# 4_mcu.net
KiCad netlist of a schematic drawn in Altium Designer
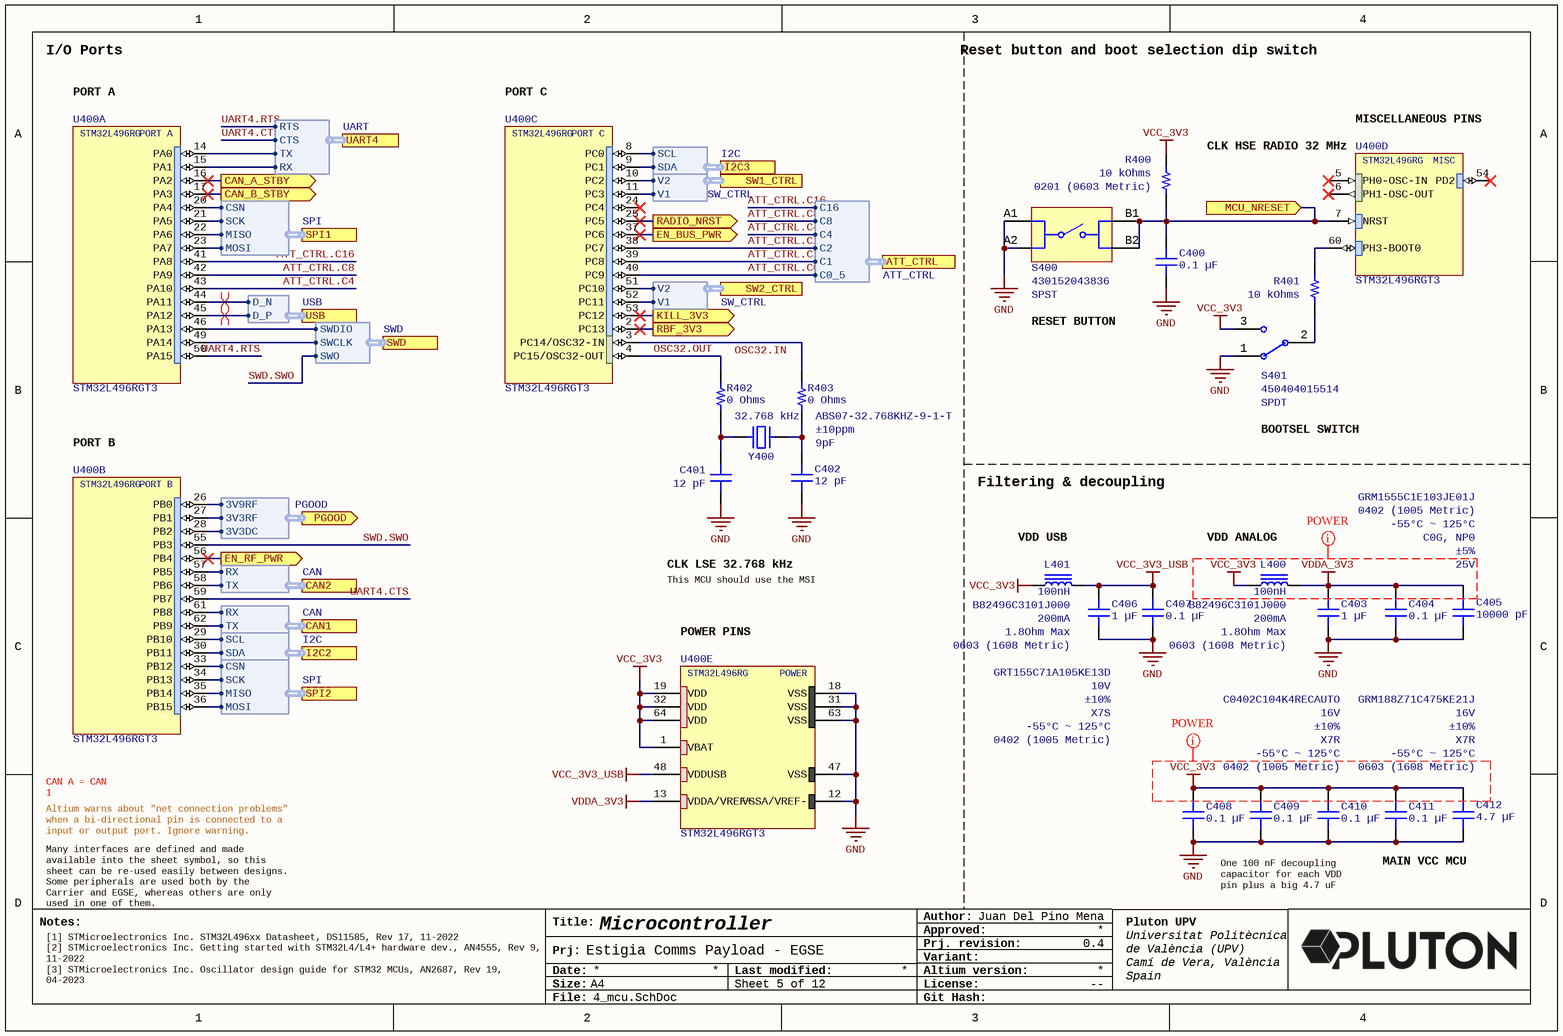
[diagram p0: 4_mcu.SchDoc]

(export (version "E")
  (design (tool "Eeschema 10.0.6"))
  (components
    (comp (ref "C400")
      (value "0.1 µF")
      (footprint "CAP 0402_1005")
      (description "CAP CER 0402 0.1UF 16V X7R 10%")
      (fields (field (name "PART NUMBER") "C0402C104K4RECAUTO") (field (name "MANUFACTURER") "KEMET"))
      (libsource (lib "Celestial Altium Library - altium_library") (part "Capacitor"))
    )
    (comp (ref "C401")
      (value "12 pF")
      (footprint "CAP 0201_0603")
      (description "CAP CER 12PF 25V C0G/NP0 0201")
      (fields (field (name "PART NUMBER") "CBR02C120F3GAC") (field (name "MANUFACTURER") "KEMET"))
      (libsource (lib "Celestial Altium Library - altium_library") (part "Capacitor"))
    )
    (comp (ref "C402")
      (value "12 pF")
      (footprint "CAP 0201_0603")
      (description "CAP CER 12PF 25V C0G/NP0 0201")
      (fields (field (name "PART NUMBER") "CBR02C120F3GAC") (field (name "MANUFACTURER") "KEMET"))
      (libsource (lib "Celestial Altium Library - altium_library") (part "Capacitor"))
    )
    (comp (ref "C403")
      (value "1 µF")
      (footprint "CAP 0402_1005")
      (description "CAP CER 1UF 10V X7S 0402")
      (fields
        (field (name "PART NUMBER") "GRT155C71A105KE13D")
        (field (name "MANUFACTURER") "Murata Electronics")
      )
      (libsource (lib "Celestial Altium Library - altium_library") (part "Capacitor"))
    )
    (comp (ref "C404")
      (value "0.1 µF")
      (footprint "CAP 0402_1005")
      (description "CAP CER 0402 0.1UF 16V X7R 10%")
      (fields (field (name "PART NUMBER") "C0402C104K4RECAUTO") (field (name "MANUFACTURER") "KEMET"))
      (libsource (lib "Celestial Altium Library - altium_library") (part "Capacitor"))
    )
    (comp (ref "C405")
      (value "10000 pF")
      (footprint "CAP 0402_1005")
      (description "CAP CER 10000PF 25V C0G/NP0 0402")
      (fields
        (field (name "PART NUMBER") "GRM1555C1E103JE01J")
        (field (name "DEVICE PACKAGE") "0402 (1005 Metric)")
        (field (name "MANUFACTURER") "Murata Electronics")
        (field (name "OPERATING TEMPERATURE") "-55°C ~ 125°C")
        (field (name "TEMPERATURE COEFFICIENT") "C0G, NP0")
        (field (name "TOLERANCE") "±5%")
        (field (name "VOLTAGE - RATED") "25V")
      )
      (libsource (lib "Celestial Altium Library - altium_library") (part "Capacitor"))
    )
    (comp (ref "C406")
      (value "1 µF")
      (footprint "CAP 0402_1005")
      (description "CAP CER 1UF 10V X7S 0402")
      (fields
        (field (name "PART NUMBER") "GRT155C71A105KE13D")
        (field (name "DEVICE PACKAGE") "0402 (1005 Metric)")
        (field (name "MANUFACTURER") "Murata Electronics")
        (field (name "OPERATING TEMPERATURE") "-55°C ~ 125°C")
        (field (name "TEMPERATURE COEFFICIENT") "X7S")
        (field (name "TOLERANCE") "±10%")
        (field (name "VOLTAGE - RATED") "10V")
      )
      (libsource (lib "Celestial Altium Library - altium_library") (part "Capacitor"))
    )
    (comp (ref "C407")
      (value "0.1 µF")
      (footprint "CAP 0402_1005")
      (description "CAP CER 0402 0.1UF 16V X7R 10%")
      (fields (field (name "PART NUMBER") "C0402C104K4RECAUTO") (field (name "MANUFACTURER") "KEMET"))
      (libsource (lib "Celestial Altium Library - altium_library") (part "Capacitor"))
    )
    (comp (ref "C408")
      (value "0.1 µF")
      (footprint "CAP 0402_1005")
      (description "CAP CER 0402 0.1UF 16V X7R 10%")
      (fields (field (name "PART NUMBER") "C0402C104K4RECAUTO") (field (name "MANUFACTURER") "KEMET"))
      (libsource (lib "Celestial Altium Library - altium_library") (part "Capacitor"))
    )
    (comp (ref "C409")
      (value "0.1 µF")
      (footprint "CAP 0402_1005")
      (description "CAP CER 0402 0.1UF 16V X7R 10%")
      (fields
        (field (name "PART NUMBER") "C0402C104K4RECAUTO")
        (field (name "MANUFACTURER") "KEMET")
        (field (name "OPERATING TEMPERATURE") "-55°C ~ 125°C")
        (field (name "PACKAGE / CASE") "0402 (1005 Metric)")
        (field (name "TEMPERATURE COEFFICIENT") "X7R")
        (field (name "TOLERANCE") "±10%")
        (field (name "VOLTAGE - RATED") "16V")
      )
      (libsource (lib "Celestial Altium Library - altium_library") (part "Capacitor"))
    )
    (comp (ref "C410")
      (value "0.1 µF")
      (footprint "CAP 0402_1005")
      (description "CAP CER 0402 0.1UF 16V X7R 10%")
      (fields (field (name "PART NUMBER") "C0402C104K4RECAUTO") (field (name "MANUFACTURER") "KEMET"))
      (libsource (lib "Celestial Altium Library - altium_library") (part "Capacitor"))
    )
    (comp (ref "C411")
      (value "0.1 µF")
      (footprint "CAP 0402_1005")
      (description "CAP CER 0402 0.1UF 16V X7R 10%")
      (fields (field (name "PART NUMBER") "C0402C104K4RECAUTO") (field (name "MANUFACTURER") "KEMET"))
      (libsource (lib "Celestial Altium Library - altium_library") (part "Capacitor"))
    )
    (comp (ref "C412")
      (value "4.7 µF")
      (footprint "CAP 0603_1608")
      (description "CAP CER 4.7UF 16V X7R 0603")
      (fields
        (field (name "PART NUMBER") "GRM188Z71C475KE21J")
        (field (name "DEVICE PACKAGE") "0603 (1608 Metric)")
        (field (name "MANUFACTURER") "Murata Electronics")
        (field (name "OPERATING TEMPERATURE") "-55°C ~ 125°C")
        (field (name "TEMPERATURE COEFFICIENT") "X7R")
        (field (name "TOLERANCE") "±10%")
        (field (name "VOLTAGE - RATED") "16V")
      )
      (libsource (lib "Celestial Altium Library - altium_library") (part "Capacitor"))
    )
    (comp (ref "L400")
      (value "100nH")
      (footprint "IND 0603_1608 RF WW")
      (description "FIXED IND 100NH 200MA 1.8 OHM")
      (fields
        (field (name "PART NUMBER") "B82496C3101J000")
        (field (name "CURRENT RATING (AMPS)") "200mA")
        (field (name "DC RESISTANCE (DCR)") "1.8Ohm Max")
        (field (name "DEVICE PACKAGE") "0603 (1608 Metric)")
        (field (name "MANUFACTURER") "TDK Electronics Inc.")
        (field (name "TOLERANCE") "±5%")
      )
      (libsource (lib "Celestial Altium Library - altium_library") (part "Inductor"))
    )
    (comp (ref "L401")
      (value "100nH")
      (footprint "IND 0603_1608 RF WW")
      (description "FIXED IND 100NH 200MA 1.8 OHM")
      (fields
        (field (name "PART NUMBER") "B82496C3101J000")
        (field (name "CURRENT RATING (AMPS)") "200mA")
        (field (name "DC RESISTANCE (DCR)") "1.8Ohm Max")
        (field (name "DEVICE PACKAGE") "0603 (1608 Metric)")
        (field (name "MANUFACTURER") "TDK Electronics Inc.")
        (field (name "TOLERANCE") "±5%")
      )
      (libsource (lib "Celestial Altium Library - altium_library") (part "Inductor"))
    )
    (comp (ref "R400")
      (value "10 kOhms")
      (footprint "RES 0201_0603")
      (description "RES SMD 10K OHM 1% 1/20W 0201")
      (fields
        (field (name "PART NUMBER") "AF0201FR-0710KL")
        (field (name "MANUFACTURER") "Yageo")
        (field (name "PACKAGE / CASE") "0201 (0603 Metric)")
      )
      (libsource (lib "Celestial Altium Library - altium_library") (part "Resistor"))
    )
    (comp (ref "R401")
      (value "10 kOhms")
      (footprint "RES 0201_0603")
      (description "RES SMD 10K OHM 1% 1/20W 0201")
      (fields (field (name "PART NUMBER") "AF0201FR-0710KL") (field (name "MANUFACTURER") "Yageo"))
      (libsource (lib "Celestial Altium Library - altium_library") (part "Resistor"))
    )
    (comp (ref "R402")
      (value "0 Ohms")
      (footprint "RES 0201_0603")
      (description "RES SMD 0 OHM JUMPER 1/20W 0201")
      (fields (field (name "PART NUMBER") "AC0201JR-070RL") (field (name "MANUFACTURER") "Yageo"))
      (libsource (lib "Celestial Altium Library - altium_library") (part "Resistor"))
    )
    (comp (ref "R403")
      (value "0 Ohms")
      (footprint "RES 0201_0603")
      (description "RES SMD 0 OHM JUMPER 1/20W 0201")
      (fields (field (name "PART NUMBER") "AC0201JR-070RL") (field (name "MANUFACTURER") "Yageo"))
      (libsource (lib "Celestial Altium Library - altium_library") (part "Resistor"))
    )
    (comp (ref "S400")
      (value "430152043836")
      (footprint "WS-TASV_L6W6H4.3_4301x20438x6")
      (fields (field (name "THROW CONFIGURATION") "SPST"))
      (libsource (lib "Altium Content Vault") (part "SPST-NO_4P"))
    )
    (comp (ref "S401")
      (value "450404015514")
      (footprint "WURTH WS-SLSU 450404015514")
      (description "MINI SLIDE SWITCH 6.7 X 2.7 MM.")
      (fields
        (field (name "PART NUMBER") "450404015514")
        (field (name "CIRCUIT") "SPDT")
        (field (name "MANUFACTURER") "Würth Elektronik")
        (field (name "PUBLISHER") "Wurth Elektronik")
      )
      (libsource (lib "Celestial Altium Library - altium_library") (part "WURTH WS-SLSU 450404015514"))
    )
    (comp (ref "U400")
      (value "STM32L496RGT3")
      (footprint "ics:LQFP64")
      (libsource (lib "stm32") (part "STM32L496RGT3"))
    )
    (comp (ref "Y400")
      (value "32.768 kHz")
      (footprint "ABRACON ABS07")
      (description "CRYSTAL 32.7680KHZ 9PF SMD")
      (fields
        (field (name "PART NUMBER") "ABS07-32.768KHZ-9-1-T")
        (field (name "FREQUENCY") "32.768 kHz")
        (field (name "FREQUENCY TOLERANCE") "±10ppm")
        (field (name "LOAD CAPACITANCE") "9pF")
        (field (name "MANUFACTURER") "Abracon LLC")
      )
      (libsource (lib "Celestial Altium Library - altium_library") (part "Abracon Crystal ABS07"))
    )
  )
  (nets
    (net (code "10") (name "/3V3DC") (class "Default")
      (node (ref "U400") (pin "28") (pinfunction "PB2_28") (pintype "bidirectional"))
    )
    (net (code "11") (name "/3V3RF") (class "Default")
      (node (ref "U400") (pin "27") (pinfunction "PB1_27") (pintype "bidirectional"))
    )
    (net (code "12") (name "/3V9RF") (class "Default")
      (node (ref "U400") (pin "26") (pinfunction "PB0_26") (pintype "bidirectional"))
    )
    (net (code "13") (name "/ATT_CTRL.C0_5") (class "Default")
      (node (ref "U400") (pin "40") (pinfunction "PC9_40") (pintype "bidirectional"))
    )
    (net (code "14") (name "/ATT_CTRL.C1") (class "Default")
      (node (ref "U400") (pin "39") (pinfunction "PC8_39") (pintype "bidirectional"))
    )
    (net (code "15") (name "/ATT_CTRL.C2") (class "Default")
      (node (ref "U400") (pin "38") (pinfunction "PC7_38") (pintype "bidirectional"))
    )
    (net (code "16") (name "/ATT_CTRL.C4") (class "Default")
      (node (ref "U400") (pin "43") (pinfunction "PA10_43") (pintype "bidirectional"))
    )
    (net (code "17") (name "/ATT_CTRL.C8") (class "Default")
      (node (ref "U400") (pin "42") (pinfunction "PA9_42") (pintype "bidirectional"))
    )
    (net (code "18") (name "/ATT_CTRL.C16") (class "Default")
      (node (ref "U400") (pin "41") (pinfunction "PA8_41") (pintype "bidirectional"))
    )
    (net (code "19") (name "/CAN_A_STBY") (class "Default")
      (node (ref "U400") (pin "16") (pinfunction "PA2_16") (pintype "bidirectional+no_connect"))
    )
    (net (code "20") (name "/CAN_B_STBY") (class "Default")
      (node (ref "U400") (pin "17") (pinfunction "PA3_17") (pintype "bidirectional+no_connect"))
    )
    (net (code "21") (name "/D_N") (class "Default")
      (node (ref "U400") (pin "44") (pinfunction "PA11_44") (pintype "bidirectional"))
    )
    (net (code "22") (name "/D_P") (class "Default")
      (node (ref "U400") (pin "45") (pinfunction "PA12_45") (pintype "bidirectional"))
    )
    (net (code "23") (name "/EN_BUS_PWR") (class "Default")
      (node (ref "U400") (pin "37") (pinfunction "PC6_37") (pintype "bidirectional+no_connect"))
    )
    (net (code "24") (name "/EN_RF_PWR") (class "Default")
      (node (ref "U400") (pin "56") (pinfunction "PB4_56") (pintype "bidirectional+no_connect"))
    )
    (net (code "26") (name "/KILL_3V3") (class "Default")
      (node (ref "U400") (pin "53") (pinfunction "PC12_53") (pintype "bidirectional+no_connect"))
    )
    (net (code "27") (name "/MCU_NRESET") (class "Default")
      (node (ref "C400") (pin "2") (pinfunction "2_2") (pintype "passive"))
      (node (ref "R400") (pin "1") (pinfunction "1_1") (pintype "passive"))
      (node (ref "S400") (pin "B1") (pinfunction "B1_B1") (pintype "passive"))
      (node (ref "S400") (pin "B2") (pinfunction "B2_B2") (pintype "passive"))
      (node (ref "U400") (pin "7") (pinfunction "NRST_7") (pintype "input"))
    )
    (net (code "28") (name "/OSC32.IN") (class "Default")
      (node (ref "R403") (pin "2") (pinfunction "2_2") (pintype "passive"))
      (node (ref "U400") (pin "3") (pinfunction "PC14/OSC32-IN_3") (pintype "bidirectional"))
    )
    (net (code "29") (name "/OSC32.OUT") (class "Default")
      (node (ref "R402") (pin "2") (pinfunction "2_2") (pintype "passive"))
      (node (ref "U400") (pin "4") (pinfunction "PC15/OSC32-OUT_4") (pintype "bidirectional"))
    )
    (net (code "30") (name "/RADIO_NRST") (class "Default")
      (node (ref "U400") (pin "25") (pinfunction "PC5_25") (pintype "bidirectional+no_connect"))
    )
    (net (code "31") (name "/RBF_3V3") (class "Default")
      (node (ref "U400") (pin "2") (pinfunction "PC13_2") (pintype "bidirectional+no_connect"))
    )
    (net (code "32") (name "/SWCLK") (class "Default")
      (node (ref "U400") (pin "49") (pinfunction "PA14_49") (pintype "bidirectional"))
    )
    (net (code "33") (name "/SWD.SWO") (class "Default")
      (node (ref "U400") (pin "55") (pinfunction "PB3_55") (pintype "bidirectional"))
    )
    (net (code "34") (name "/SWDIO") (class "Default")
      (node (ref "U400") (pin "46") (pinfunction "PA13_46") (pintype "bidirectional"))
    )
    (net (code "35") (name "/UART4.CTS") (class "Default")
      (node (ref "U400") (pin "59") (pinfunction "PB7_59") (pintype "bidirectional"))
    )
    (net (code "36") (name "/UART4.RTS") (class "Default")
      (node (ref "U400") (pin "50") (pinfunction "PA15_50") (pintype "bidirectional"))
    )
    (net (code "45") (name "GND") (class "Default")
      (node (ref "C400") (pin "1") (pinfunction "1_1") (pintype "passive"))
      (node (ref "C401") (pin "1") (pinfunction "1_1") (pintype "passive"))
      (node (ref "C402") (pin "1") (pinfunction "1_1") (pintype "passive"))
      (node (ref "C403") (pin "1") (pinfunction "1_1") (pintype "passive"))
      (node (ref "C404") (pin "1") (pinfunction "1_1") (pintype "passive"))
      (node (ref "C405") (pin "1") (pinfunction "1_1") (pintype "passive"))
      (node (ref "C406") (pin "1") (pinfunction "1_1") (pintype "passive"))
      (node (ref "C407") (pin "1") (pinfunction "1_1") (pintype "passive"))
      (node (ref "C408") (pin "1") (pinfunction "1_1") (pintype "passive"))
      (node (ref "C409") (pin "1") (pinfunction "1_1") (pintype "passive"))
      (node (ref "C410") (pin "1") (pinfunction "1_1") (pintype "passive"))
      (node (ref "C411") (pin "1") (pinfunction "1_1") (pintype "passive"))
      (node (ref "C412") (pin "1") (pinfunction "1_1") (pintype "passive"))
      (node (ref "S400") (pin "A1") (pinfunction "A1_A1") (pintype "passive"))
      (node (ref "S400") (pin "A2") (pinfunction "A2_A2") (pintype "passive"))
      (node (ref "S401") (pin "1") (pinfunction "1_1") (pintype "passive"))
      (node (ref "U400") (pin "12") (pinfunction "VSSA/VREF-_12") (pintype "power_in"))
      (node (ref "U400") (pin "18") (pinfunction "VSS_18") (pintype "power_in"))
      (node (ref "U400") (pin "31") (pinfunction "VSS_31") (pintype "power_in"))
      (node (ref "U400") (pin "47") (pinfunction "VSS_47") (pintype "power_in"))
      (node (ref "U400") (pin "63") (pinfunction "VSS_63") (pintype "power_in"))
    )
    (net (code "46") (name "Net-(C401-Pad2)") (class "Default")
      (node (ref "C401") (pin "2") (pinfunction "2_2") (pintype "passive"))
      (node (ref "R402") (pin "1") (pinfunction "1_1") (pintype "passive"))
      (node (ref "Y400") (pin "1") (pinfunction "1_1") (pintype "passive"))
    )
    (net (code "47") (name "Net-(C402-Pad2)") (class "Default")
      (node (ref "C402") (pin "2") (pinfunction "2_2") (pintype "passive"))
      (node (ref "R403") (pin "1") (pinfunction "1_1") (pintype "passive"))
      (node (ref "Y400") (pin "2") (pinfunction "2_2") (pintype "passive"))
    )
    (net (code "48") (name "Net-(S401-COM)") (class "Default")
      (node (ref "R401") (pin "1") (pinfunction "1_1") (pintype "passive"))
      (node (ref "S401") (pin "2") (pinfunction "COM_2") (pintype "passive"))
    )
    (net (code "49") (name "Net-(U400D-PH3-BOOT0)") (class "Default")
      (node (ref "R401") (pin "2") (pinfunction "2_2") (pintype "passive"))
      (node (ref "U400") (pin "60") (pinfunction "PH3-BOOT0_60") (pintype "bidirectional"))
    )
    (net (code "50") (name "VCC_3V3") (class "Default")
      (node (ref "C408") (pin "2") (pinfunction "2_2") (pintype "passive"))
      (node (ref "C409") (pin "2") (pinfunction "2_2") (pintype "passive"))
      (node (ref "C410") (pin "2") (pinfunction "2_2") (pintype "passive"))
      (node (ref "C411") (pin "2") (pinfunction "2_2") (pintype "passive"))
      (node (ref "C412") (pin "2") (pinfunction "2_2") (pintype "passive"))
      (node (ref "L400") (pin "1") (pinfunction "1_1") (pintype "passive"))
      (node (ref "L401") (pin "1") (pinfunction "1_1") (pintype "passive"))
      (node (ref "R400") (pin "2") (pinfunction "2_2") (pintype "passive"))
      (node (ref "S401") (pin "3") (pinfunction "3_3") (pintype "passive"))
      (node (ref "U400") (pin "1") (pinfunction "VBAT_1") (pintype "power_in"))
      (node (ref "U400") (pin "19") (pinfunction "VDD_19") (pintype "power_in"))
      (node (ref "U400") (pin "32") (pinfunction "VDD_32") (pintype "power_in"))
      (node (ref "U400") (pin "64") (pinfunction "VDD_64") (pintype "power_in"))
    )
    (net (code "51") (name "VCC_3V3_USB") (class "Default")
      (node (ref "C406") (pin "2") (pinfunction "2_2") (pintype "passive"))
      (node (ref "C407") (pin "2") (pinfunction "2_2") (pintype "passive"))
      (node (ref "L401") (pin "2") (pinfunction "2_2") (pintype "passive"))
      (node (ref "U400") (pin "48") (pinfunction "VDDUSB_48") (pintype "power_in"))
    )
    (net (code "52") (name "VDDA_3V3") (class "Default")
      (node (ref "C403") (pin "2") (pinfunction "2_2") (pintype "passive"))
      (node (ref "C404") (pin "2") (pinfunction "2_2") (pintype "passive"))
      (node (ref "C405") (pin "2") (pinfunction "2_2") (pintype "passive"))
      (node (ref "L400") (pin "2") (pinfunction "2_2") (pintype "passive"))
      (node (ref "U400") (pin "13") (pinfunction "VDDA/VREF+_13") (pintype "power_in"))
    )
    (net (code "53") (name "unconnected-(U400A-PA0-Pad14)") (class "Default")
      (node (ref "U400") (pin "14") (pinfunction "PA0_14") (pintype "bidirectional"))
    )
    (net (code "54") (name "unconnected-(U400A-PA1-Pad15)") (class "Default")
      (node (ref "U400") (pin "15") (pinfunction "PA1_15") (pintype "bidirectional"))
    )
    (net (code "55") (name "unconnected-(U400A-PA4-Pad20)") (class "Default")
      (node (ref "U400") (pin "20") (pinfunction "PA4_20") (pintype "bidirectional"))
    )
    (net (code "56") (name "unconnected-(U400A-PA5-Pad21)") (class "Default")
      (node (ref "U400") (pin "21") (pinfunction "PA5_21") (pintype "bidirectional"))
    )
    (net (code "57") (name "unconnected-(U400A-PA6-Pad22)") (class "Default")
      (node (ref "U400") (pin "22") (pinfunction "PA6_22") (pintype "bidirectional"))
    )
    (net (code "58") (name "unconnected-(U400A-PA7-Pad23)") (class "Default")
      (node (ref "U400") (pin "23") (pinfunction "PA7_23") (pintype "bidirectional"))
    )
    (net (code "59") (name "unconnected-(U400B-PB5-Pad57)") (class "Default")
      (node (ref "U400") (pin "57") (pinfunction "PB5_57") (pintype "bidirectional"))
    )
    (net (code "60") (name "unconnected-(U400B-PB6-Pad58)") (class "Default")
      (node (ref "U400") (pin "58") (pinfunction "PB6_58") (pintype "bidirectional"))
    )
    (net (code "61") (name "unconnected-(U400B-PB8-Pad61)") (class "Default")
      (node (ref "U400") (pin "61") (pinfunction "PB8_61") (pintype "bidirectional"))
    )
    (net (code "62") (name "unconnected-(U400B-PB9-Pad62)") (class "Default")
      (node (ref "U400") (pin "62") (pinfunction "PB9_62") (pintype "bidirectional"))
    )
    (net (code "63") (name "unconnected-(U400B-PB10-Pad29)") (class "Default")
      (node (ref "U400") (pin "29") (pinfunction "PB10_29") (pintype "bidirectional"))
    )
    (net (code "64") (name "unconnected-(U400B-PB11-Pad30)") (class "Default")
      (node (ref "U400") (pin "30") (pinfunction "PB11_30") (pintype "bidirectional"))
    )
    (net (code "65") (name "unconnected-(U400B-PB12-Pad33)") (class "Default")
      (node (ref "U400") (pin "33") (pinfunction "PB12_33") (pintype "bidirectional"))
    )
    (net (code "66") (name "unconnected-(U400B-PB13-Pad34)") (class "Default")
      (node (ref "U400") (pin "34") (pinfunction "PB13_34") (pintype "bidirectional"))
    )
    (net (code "67") (name "unconnected-(U400B-PB14-Pad35)") (class "Default")
      (node (ref "U400") (pin "35") (pinfunction "PB14_35") (pintype "bidirectional"))
    )
    (net (code "68") (name "unconnected-(U400B-PB15-Pad36)") (class "Default")
      (node (ref "U400") (pin "36") (pinfunction "PB15_36") (pintype "bidirectional"))
    )
    (net (code "69") (name "unconnected-(U400C-PC0-Pad8)") (class "Default")
      (node (ref "U400") (pin "8") (pinfunction "PC0_8") (pintype "bidirectional"))
    )
    (net (code "70") (name "unconnected-(U400C-PC1-Pad9)") (class "Default")
      (node (ref "U400") (pin "9") (pinfunction "PC1_9") (pintype "bidirectional"))
    )
    (net (code "71") (name "unconnected-(U400C-PC2-Pad10)") (class "Default")
      (node (ref "U400") (pin "10") (pinfunction "PC2_10") (pintype "bidirectional"))
    )
    (net (code "72") (name "unconnected-(U400C-PC3-Pad11)") (class "Default")
      (node (ref "U400") (pin "11") (pinfunction "PC3_11") (pintype "bidirectional"))
    )
    (net (code "73") (name "unconnected-(U400C-PC4-Pad24)") (class "Default")
      (node (ref "U400") (pin "24") (pinfunction "PC4_24") (pintype "bidirectional+no_connect"))
    )
    (net (code "74") (name "unconnected-(U400C-PC10-Pad51)") (class "Default")
      (node (ref "U400") (pin "51") (pinfunction "PC10_51") (pintype "bidirectional"))
    )
    (net (code "75") (name "unconnected-(U400C-PC11-Pad52)") (class "Default")
      (node (ref "U400") (pin "52") (pinfunction "PC11_52") (pintype "bidirectional"))
    )
    (net (code "76") (name "unconnected-(U400D-PD2-Pad54)") (class "Default")
      (node (ref "U400") (pin "54") (pinfunction "PD2_54") (pintype "bidirectional+no_connect"))
    )
    (net (code "77") (name "unconnected-(U400D-PH0-OSC-IN-Pad5)") (class "Default")
      (node (ref "U400") (pin "5") (pinfunction "PH0-OSC-IN_5") (pintype "input+no_connect"))
    )
    (net (code "78") (name "unconnected-(U400D-PH1-OSC-OUT-Pad6)") (class "Default")
      (node (ref "U400") (pin "6") (pinfunction "PH1-OSC-OUT_6") (pintype "output+no_connect"))
    )
  )
)
